# schematic.net
KiCad netlist of a schematic drawn in Altium Designer
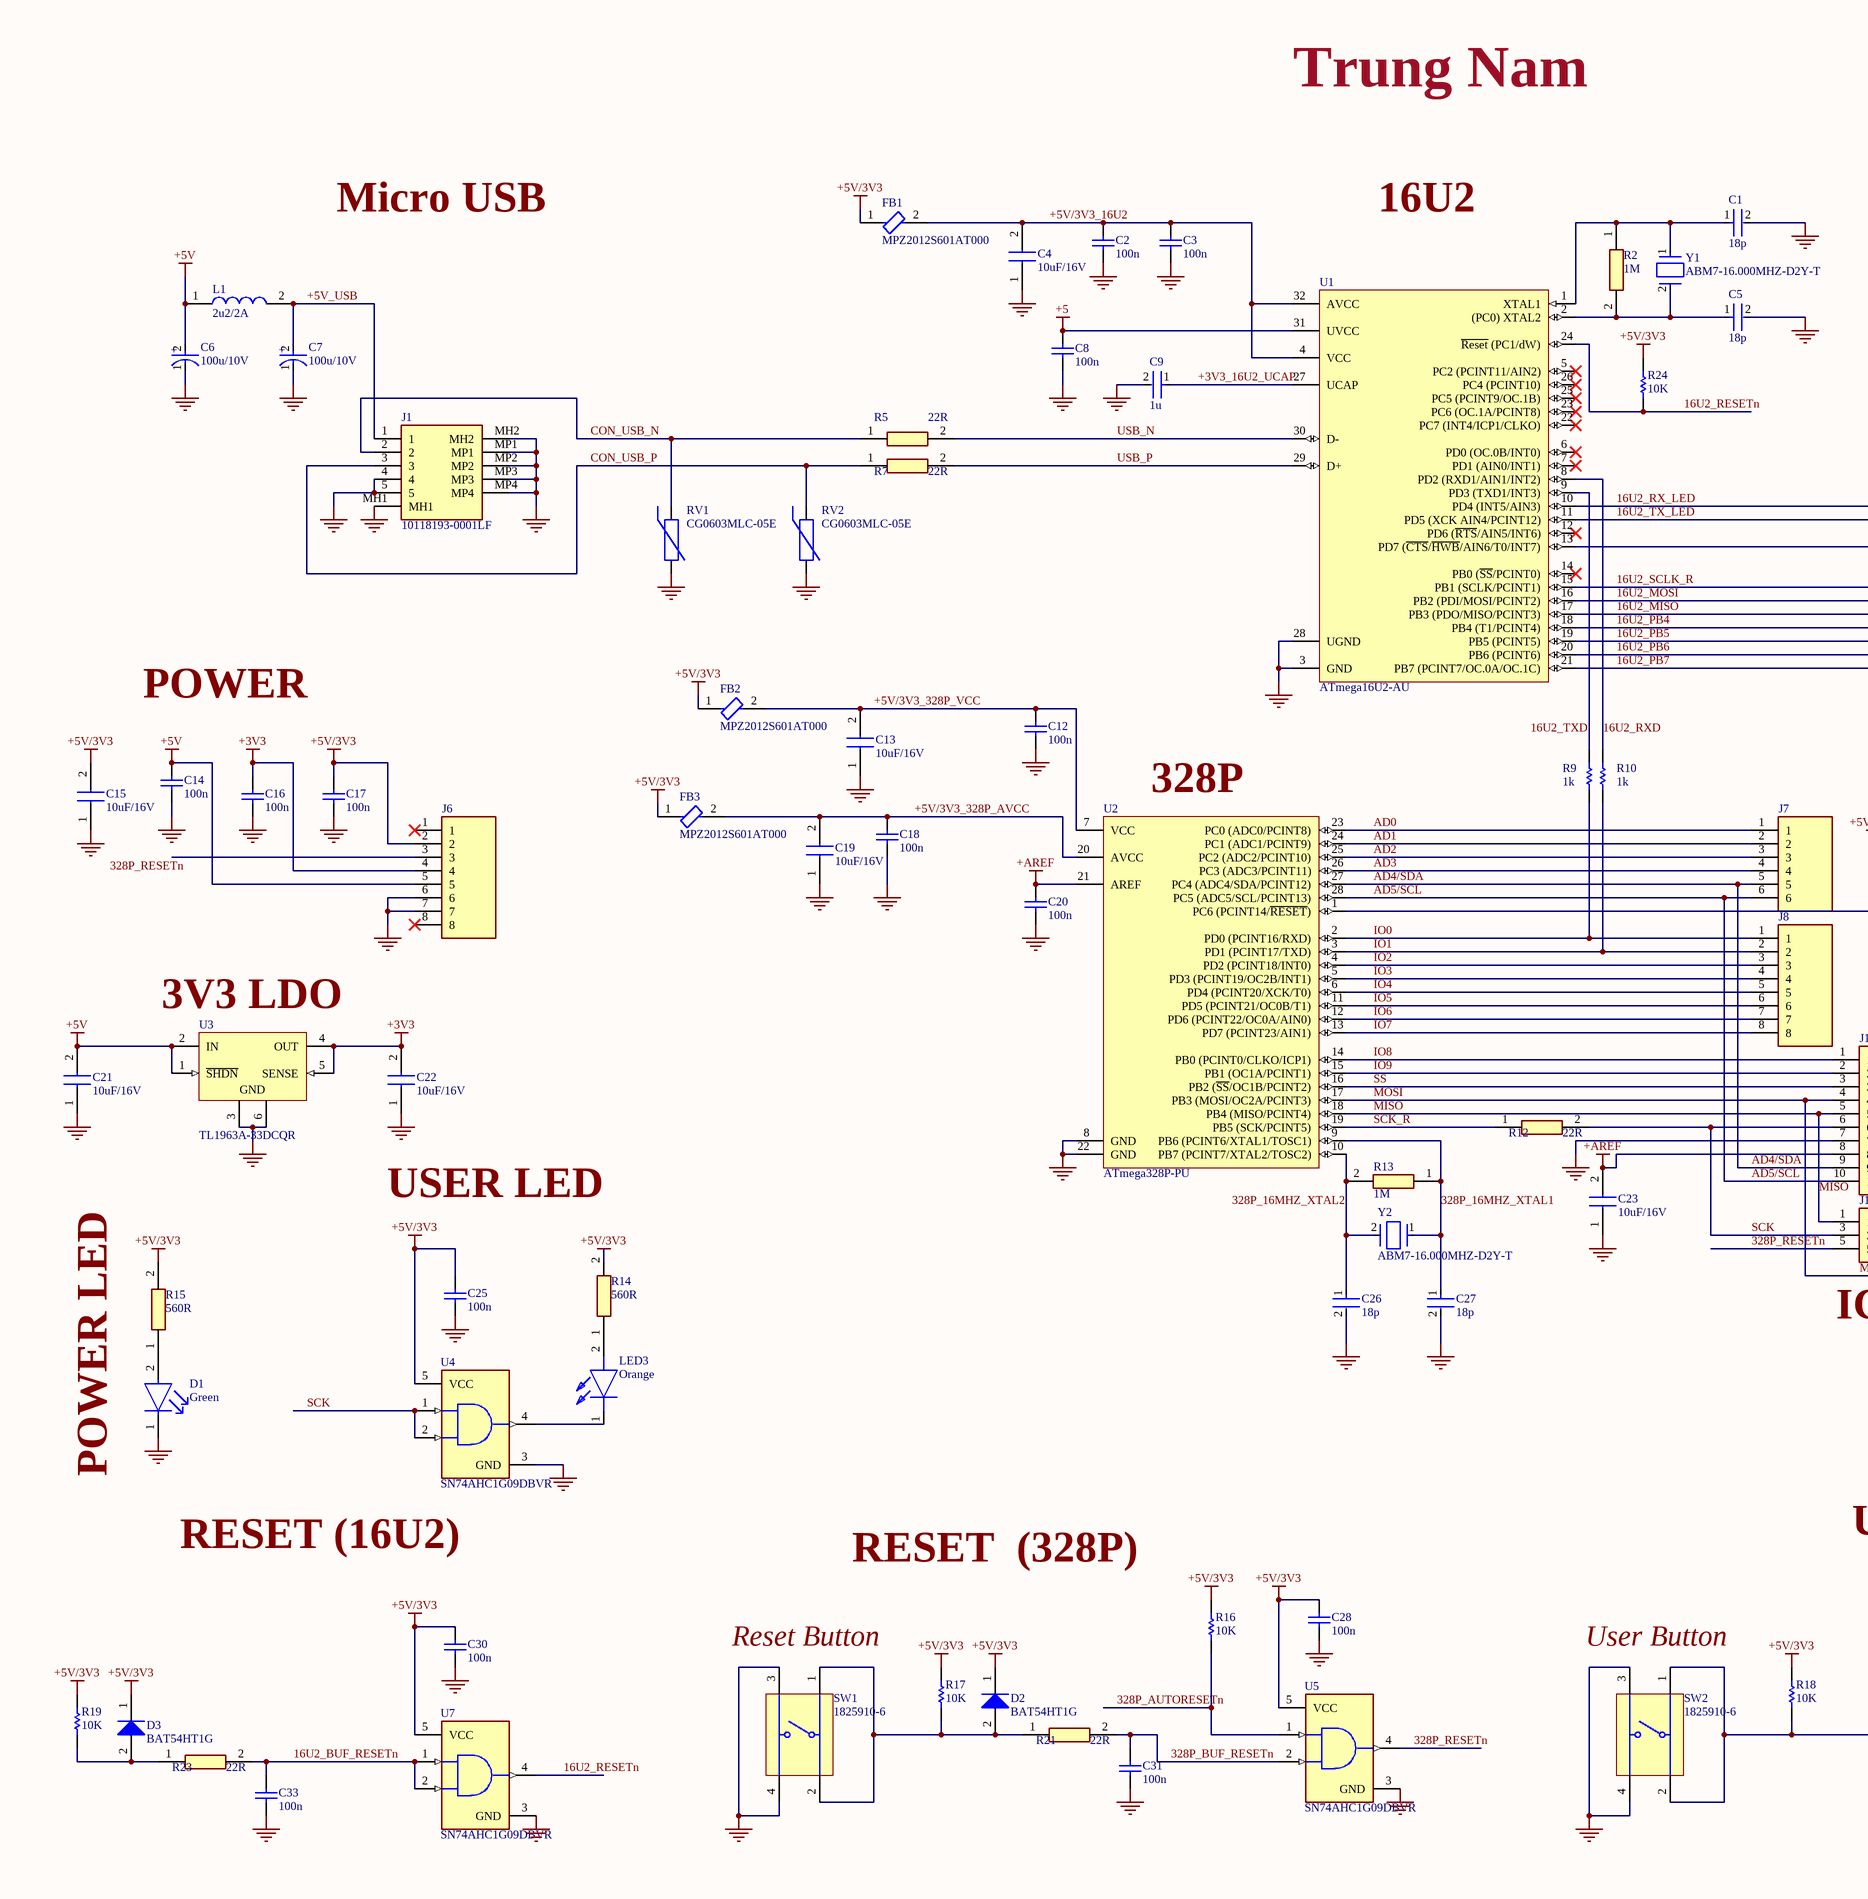
[diagram p0: schematic.SchDoc, left]
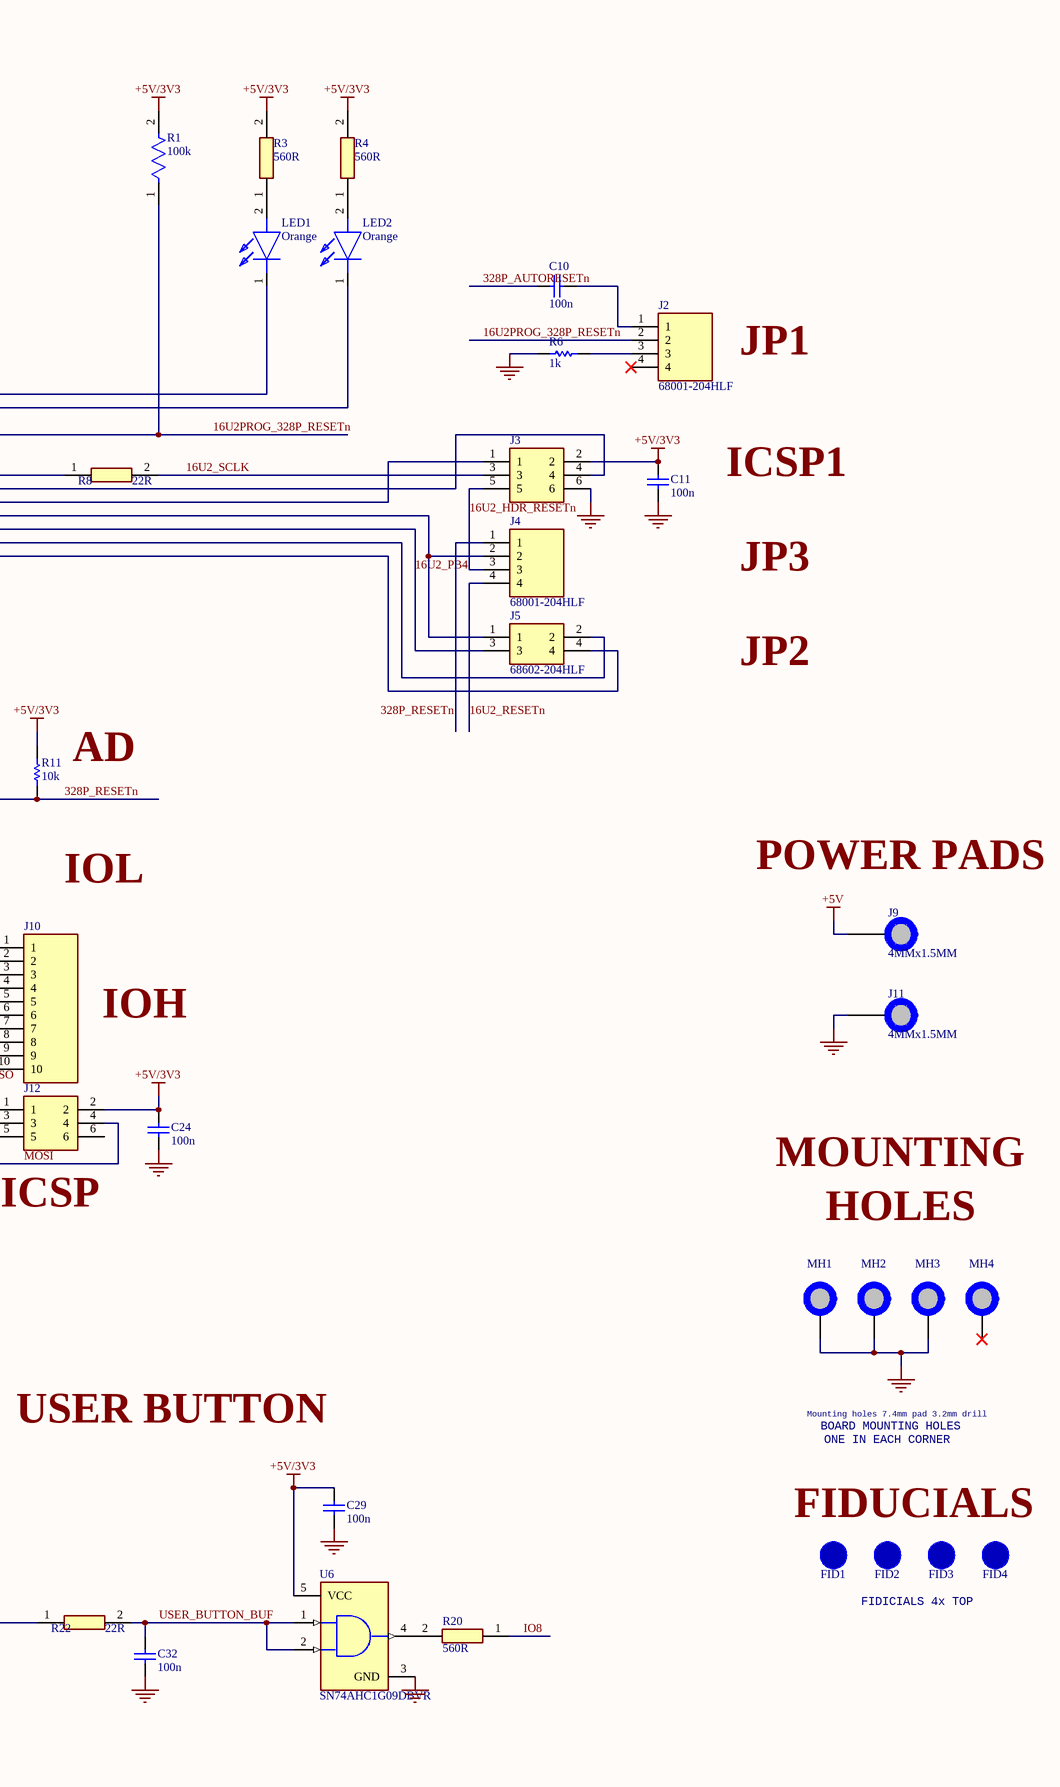
[diagram p1: schematic.SchDoc, right]

(export (version "E")
  (design (tool "Eeschema 10.0.6"))
  (components
    (comp (ref "C1")
      (value "18p")
      (footprint "FP-C0805C-DN-MFG")
      (description "CAP CER 18PF 50V C0G/NP0 0805")
      (fields
        (field (name "OCTOPART") "https://octopart.com/c0805c180j5gactu-kemet-144810")
        (field (name "TOLERANCE") "0.05")
      )
      (libsource (lib "Altium Content Vault") (part "b4654b650e69147ec39a6b967a45e02"))
    )
    (comp (ref "C2")
      (value "100n")
      (footprint "CAPC2013X145X20LL20")
      (description "Chip Capacitor, 0.1 uF, +/- 10%, 50 V, -55 to 125 degC, 0805 (2012 Metric), RoHS, Tape and Reel")
      (fields (field (name "MANUFACTURER") "TDK") (field (name "VOLTAGE") "50V"))
      (libsource (lib "Altium Content Vault") (part "CAP-NP-2"))
    )
    (comp (ref "C3")
      (value "100n")
      (footprint "CAPC2013X145X20LL20")
      (description "Chip Capacitor, 0.1 uF, +/- 10%, 50 V, -55 to 125 degC, 0805 (2012 Metric), RoHS, Tape and Reel")
      (fields (field (name "MANUFACTURER") "TDK") (field (name "VOLTAGE") "50V"))
      (libsource (lib "Altium Content Vault") (part "CAP-NP-2"))
    )
    (comp (ref "C4")
      (value "10uF/16V")
      (footprint "SamacSys:CAPC2012X145N")
      (description "Capacitor")
      (fields
        (field (name "MANUFACTURER_PART_NUMBER") "C2012X5R1C106M125AC")
        (field (name "MOUSER PART NUMBER") "810-C2012X5R1C106M-3")
      )
      (libsource (lib "SamacSys") (part "C2012X5R1C106M125AC"))
    )
    (comp (ref "C5")
      (value "18p")
      (footprint "FP-C0805C-DN-MFG")
      (description "CAP CER 18PF 50V C0G/NP0 0805")
      (fields
        (field (name "OCTOPART") "https://octopart.com/c0805c180j5gactu-kemet-144810")
        (field (name "TOLERANCE") "0.05")
      )
      (libsource (lib "Altium Content Vault") (part "b4654b650e69147ec39a6b967a45e02"))
    )
    (comp (ref "C6")
      (value "100u/10V")
      (footprint "FP-SC-MFG")
      (description "CAP ALUM 100UF 20% 10V SMD")
      (fields (field (name "TOLERANCE") "20%"))
      (libsource (lib "Altium Content Vault") (part "a00bbbee19879c290e62620ae7e47b1"))
    )
    (comp (ref "C7")
      (value "100u/10V")
      (footprint "FP-SC-MFG")
      (description "CAP ALUM 100UF 20% 10V SMD")
      (fields (field (name "TOLERANCE") "20%"))
      (libsource (lib "Altium Content Vault") (part "a00bbbee19879c290e62620ae7e47b1"))
    )
    (comp (ref "C8")
      (value "100n")
      (footprint "CAPC2013X145X20LL20")
      (description "Chip Capacitor, 0.1 uF, +/- 10%, 50 V, -55 to 125 degC, 0805 (2012 Metric), RoHS, Tape and Reel")
      (fields (field (name "MANUFACTURER") "TDK") (field (name "VOLTAGE") "50V"))
      (libsource (lib "Altium Content Vault") (part "CAP-NP-2"))
    )
    (comp (ref "C9")
      (value "1u")
      (footprint "FP-C2012-125-0_2-IPC_A")
      (description "Multilayer Ceramic Capacitors 1μF ±10% 25V X5R SMD 0805")
      (fields (field (name "VOLTAGE") "25V") (field (name "TOLERANCE") "10%"))
      (libsource (lib "Altium Content Vault") (part "b4654b650e69147ec39a6b967a45e02"))
    )
    (comp (ref "C10")
      (value "100n")
      (footprint "CAPC2013X145X20LL20")
      (description "Chip Capacitor, 0.1 uF, +/- 10%, 50 V, -55 to 125 degC, 0805 (2012 Metric), RoHS, Tape and Reel")
      (fields (field (name "MANUFACTURER") "TDK") (field (name "VOLTAGE") "50V"))
      (libsource (lib "Altium Content Vault") (part "CAP-NP-2"))
    )
    (comp (ref "C11")
      (value "100n")
      (footprint "CAPC2013X145X20LL20")
      (description "Chip Capacitor, 0.1 uF, +/- 10%, 50 V, -55 to 125 degC, 0805 (2012 Metric), RoHS, Tape and Reel")
      (fields (field (name "MANUFACTURER") "TDK") (field (name "VOLTAGE") "50V"))
      (libsource (lib "Altium Content Vault") (part "CAP-NP-2"))
    )
    (comp (ref "C12")
      (value "100n")
      (footprint "CAPC2013X145X20LL20")
      (description "Chip Capacitor, 0.1 uF, +/- 10%, 50 V, -55 to 125 degC, 0805 (2012 Metric), RoHS, Tape and Reel")
      (fields (field (name "MANUFACTURER") "TDK") (field (name "VOLTAGE") "50V"))
      (libsource (lib "Altium Content Vault") (part "CAP-NP-2"))
    )
    (comp (ref "C13")
      (value "10uF/16V")
      (footprint "SamacSys:CAPC2012X145N")
      (description "Capacitor")
      (fields
        (field (name "MANUFACTURER_PART_NUMBER") "C2012X5R1C106M125AC")
        (field (name "MOUSER PART NUMBER") "810-C2012X5R1C106M-3")
      )
      (libsource (lib "SamacSys") (part "C2012X5R1C106M125AC"))
    )
    (comp (ref "C14")
      (value "100n")
      (footprint "CAPC2013X145X20LL20")
      (description "Chip Capacitor, 0.1 uF, +/- 10%, 50 V, -55 to 125 degC, 0805 (2012 Metric), RoHS, Tape and Reel")
      (fields (field (name "MANUFACTURER") "TDK") (field (name "VOLTAGE") "50V"))
      (libsource (lib "Altium Content Vault") (part "CAP-NP-2"))
    )
    (comp (ref "C15")
      (value "10uF/16V")
      (footprint "SamacSys:CAPC2012X145N")
      (description "Capacitor")
      (fields
        (field (name "MANUFACTURER_PART_NUMBER") "C2012X5R1C106M125AC")
        (field (name "MOUSER PART NUMBER") "810-C2012X5R1C106M-3")
      )
      (libsource (lib "SamacSys") (part "C2012X5R1C106M125AC"))
    )
    (comp (ref "C16")
      (value "100n")
      (footprint "CAPC2013X145X20LL20")
      (description "Chip Capacitor, 0.1 uF, +/- 10%, 50 V, -55 to 125 degC, 0805 (2012 Metric), RoHS, Tape and Reel")
      (fields (field (name "MANUFACTURER") "TDK") (field (name "VOLTAGE") "50V"))
      (libsource (lib "Altium Content Vault") (part "CAP-NP-2"))
    )
    (comp (ref "C17")
      (value "100n")
      (footprint "CAPC2013X145X20LL20")
      (description "Chip Capacitor, 0.1 uF, +/- 10%, 50 V, -55 to 125 degC, 0805 (2012 Metric), RoHS, Tape and Reel")
      (fields (field (name "MANUFACTURER") "TDK") (field (name "VOLTAGE") "50V"))
      (libsource (lib "Altium Content Vault") (part "CAP-NP-2"))
    )
    (comp (ref "C18")
      (value "100n")
      (footprint "CAPC2013X145X20LL20")
      (description "Chip Capacitor, 0.1 uF, +/- 10%, 50 V, -55 to 125 degC, 0805 (2012 Metric), RoHS, Tape and Reel")
      (fields (field (name "MANUFACTURER") "TDK") (field (name "VOLTAGE") "50V"))
      (libsource (lib "Altium Content Vault") (part "CAP-NP-2"))
    )
    (comp (ref "C19")
      (value "10uF/16V")
      (footprint "SamacSys:CAPC2012X145N")
      (description "Capacitor")
      (fields
        (field (name "MANUFACTURER_PART_NUMBER") "C2012X5R1C106M125AC")
        (field (name "MOUSER PART NUMBER") "810-C2012X5R1C106M-3")
      )
      (libsource (lib "SamacSys") (part "C2012X5R1C106M125AC"))
    )
    (comp (ref "C20")
      (value "100n")
      (footprint "CAPC2013X145X20LL20")
      (description "Chip Capacitor, 0.1 uF, +/- 10%, 50 V, -55 to 125 degC, 0805 (2012 Metric), RoHS, Tape and Reel")
      (fields (field (name "MANUFACTURER") "TDK") (field (name "VOLTAGE") "50V"))
      (libsource (lib "Altium Content Vault") (part "CAP-NP-2"))
    )
    (comp (ref "C21")
      (value "10uF/16V")
      (footprint "SamacSys:CAPC2012X145N")
      (description "Capacitor")
      (fields
        (field (name "MANUFACTURER_PART_NUMBER") "C2012X5R1C106M125AC")
        (field (name "MOUSER PART NUMBER") "810-C2012X5R1C106M-3")
      )
      (libsource (lib "SamacSys") (part "C2012X5R1C106M125AC"))
    )
    (comp (ref "C22")
      (value "10uF/16V")
      (footprint "SamacSys:CAPC2012X145N")
      (description "Capacitor")
      (fields
        (field (name "MANUFACTURER_PART_NUMBER") "C2012X5R1C106M125AC")
        (field (name "MOUSER PART NUMBER") "810-C2012X5R1C106M-3")
      )
      (libsource (lib "SamacSys") (part "C2012X5R1C106M125AC"))
    )
    (comp (ref "C23")
      (value "10uF/16V")
      (footprint "SamacSys:CAPC2012X145N")
      (description "Capacitor")
      (fields
        (field (name "MANUFACTURER_PART_NUMBER") "C2012X5R1C106M125AC")
        (field (name "MOUSER PART NUMBER") "810-C2012X5R1C106M-3")
      )
      (libsource (lib "SamacSys") (part "C2012X5R1C106M125AC"))
    )
    (comp (ref "C24")
      (value "100n")
      (footprint "CAPC2013X145X20LL20")
      (description "Chip Capacitor, 0.1 uF, +/- 10%, 50 V, -55 to 125 degC, 0805 (2012 Metric), RoHS, Tape and Reel")
      (fields (field (name "MANUFACTURER") "TDK") (field (name "VOLTAGE") "50V"))
      (libsource (lib "Altium Content Vault") (part "CAP-NP-2"))
    )
    (comp (ref "C25")
      (value "100n")
      (footprint "CAPC2013X145X20LL20")
      (description "Chip Capacitor, 0.1 uF, +/- 10%, 50 V, -55 to 125 degC, 0805 (2012 Metric), RoHS, Tape and Reel")
      (fields (field (name "MANUFACTURER") "TDK") (field (name "VOLTAGE") "50V"))
      (libsource (lib "Altium Content Vault") (part "CAP-NP-2"))
    )
    (comp (ref "C26")
      (value "18p")
      (footprint "FP-C0805C-DN-MFG")
      (description "CAP CER 18PF 50V C0G/NP0 0805")
      (fields
        (field (name "OCTOPART") "https://octopart.com/c0805c180j5gactu-kemet-144810")
        (field (name "TOLERANCE") "0.05")
      )
      (libsource (lib "Altium Content Vault") (part "b4654b650e69147ec39a6b967a45e02"))
    )
    (comp (ref "C27")
      (value "18p")
      (footprint "FP-C0805C-DN-MFG")
      (description "CAP CER 18PF 50V C0G/NP0 0805")
      (fields
        (field (name "OCTOPART") "https://octopart.com/c0805c180j5gactu-kemet-144810")
        (field (name "TOLERANCE") "0.05")
      )
      (libsource (lib "Altium Content Vault") (part "b4654b650e69147ec39a6b967a45e02"))
    )
    (comp (ref "C28")
      (value "100n")
      (footprint "CAPC2013X145X20LL20")
      (description "Chip Capacitor, 0.1 uF, +/- 10%, 50 V, -55 to 125 degC, 0805 (2012 Metric), RoHS, Tape and Reel")
      (fields (field (name "MANUFACTURER") "TDK") (field (name "VOLTAGE") "50V"))
      (libsource (lib "Altium Content Vault") (part "CAP-NP-2"))
    )
    (comp (ref "C29")
      (value "100n")
      (footprint "CAPC2013X145X20LL20")
      (description "Chip Capacitor, 0.1 uF, +/- 10%, 50 V, -55 to 125 degC, 0805 (2012 Metric), RoHS, Tape and Reel")
      (fields (field (name "MANUFACTURER") "TDK") (field (name "VOLTAGE") "50V"))
      (libsource (lib "Altium Content Vault") (part "CAP-NP-2"))
    )
    (comp (ref "C30")
      (value "100n")
      (footprint "CAPC2013X145X20LL20")
      (description "Chip Capacitor, 0.1 uF, +/- 10%, 50 V, -55 to 125 degC, 0805 (2012 Metric), RoHS, Tape and Reel")
      (fields (field (name "MANUFACTURER") "TDK") (field (name "VOLTAGE") "50V"))
      (libsource (lib "Altium Content Vault") (part "CAP-NP-2"))
    )
    (comp (ref "C31")
      (value "100n")
      (footprint "CAPC2013X145X20LL20")
      (description "Chip Capacitor, 0.1 uF, +/- 10%, 50 V, -55 to 125 degC, 0805 (2012 Metric), RoHS, Tape and Reel")
      (fields (field (name "MANUFACTURER") "TDK") (field (name "VOLTAGE") "50V"))
      (libsource (lib "Altium Content Vault") (part "CAP-NP-2"))
    )
    (comp (ref "C32")
      (value "100n")
      (footprint "CAPC2013X145X20LL20")
      (description "Chip Capacitor, 0.1 uF, +/- 10%, 50 V, -55 to 125 degC, 0805 (2012 Metric), RoHS, Tape and Reel")
      (fields (field (name "MANUFACTURER") "TDK") (field (name "VOLTAGE") "50V"))
      (libsource (lib "Altium Content Vault") (part "CAP-NP-2"))
    )
    (comp (ref "C33")
      (value "100n")
      (footprint "CAPC2013X145X20LL20")
      (description "Chip Capacitor, 0.1 uF, +/- 10%, 50 V, -55 to 125 degC, 0805 (2012 Metric), RoHS, Tape and Reel")
      (fields (field (name "MANUFACTURER") "TDK") (field (name "VOLTAGE") "50V"))
      (libsource (lib "Altium Content Vault") (part "CAP-NP-2"))
    )
    (comp (ref "D1")
      (value "Green")
      (footprint "FP-LG_L29K-MFG")
      (description "LED GREEN DIFFUSED 0603 SMD")
      (libsource (lib "Altium Content Vault") (part "8706943c75ba83719d021d2fdc84c58"))
    )
    (comp (ref "D2")
      (value "BAT54HT1G")
      (footprint "ONSC-SOD-323-2-477-02_V")
      (description "Schottky Barrier Diode, 2-Pin SOD-323, Pb-Free, Tape and Reel")
      (fields (field (name "MANUFACTURER") "On Semiconductor"))
      (libsource (lib "Altium Content Vault") (part "ONSC-D-K1A2-2"))
    )
    (comp (ref "D3")
      (value "BAT54HT1G")
      (footprint "ONSC-SOD-323-2-477-02_V")
      (description "Schottky Barrier Diode, 2-Pin SOD-323, Pb-Free, Tape and Reel")
      (fields (field (name "MANUFACTURER") "On Semiconductor"))
      (libsource (lib "Altium Content Vault") (part "ONSC-D-K1A2-2"))
    )
    (comp (ref "FB1")
      (value "MPZ2012S601AT000")
      (footprint "FP-MPZ2012-MFG")
      (fields (field (name "TOLERANCE") "25%"))
      (libsource (lib "Altium Content Vault") (part "5f30dd21d616792df468990f7003faa"))
    )
    (comp (ref "FB2")
      (value "MPZ2012S601AT000")
      (footprint "FP-MPZ2012-MFG")
      (fields (field (name "TOLERANCE") "25%"))
      (libsource (lib "Altium Content Vault") (part "5f30dd21d616792df468990f7003faa"))
    )
    (comp (ref "FB3")
      (value "MPZ2012S601AT000")
      (footprint "FP-MPZ2012-MFG")
      (fields (field (name "TOLERANCE") "25%"))
      (libsource (lib "Altium Content Vault") (part "5f30dd21d616792df468990f7003faa"))
    )
    (comp (ref "FID1")
      (value "FID_1MMC")
      (footprint "FID_40X120D")
      (description "Fiducial 40mil Diameter, 120mil Mask")
      (libsource (lib "Integrated_Library_FEDEVEL_APR_2015") (part "FID_1MMC"))
    )
    (comp (ref "FID2")
      (value "FID_1MMC")
      (footprint "FID_40X120D")
      (description "Fiducial 40mil Diameter, 120mil Mask")
      (libsource (lib "Integrated_Library_FEDEVEL_APR_2015") (part "FID_1MMC"))
    )
    (comp (ref "FID3")
      (value "FID_1MMC")
      (footprint "FID_40X120D")
      (description "Fiducial 40mil Diameter, 120mil Mask")
      (libsource (lib "Integrated_Library_FEDEVEL_APR_2015") (part "FID_1MMC"))
    )
    (comp (ref "FID4")
      (value "FID_1MMC")
      (footprint "FID_40X120D")
      (description "Fiducial 40mil Diameter, 120mil Mask")
      (libsource (lib "Integrated_Library_FEDEVEL_APR_2015") (part "FID_1MMC"))
    )
    (comp (ref "J1")
      (value "10118193-0001LF")
      (footprint "SamacSys:101181930001LF")
      (description "Connector")
      (libsource (lib "*") (part "10118193-0001LF"))
    )
    (comp (ref "J2")
      (value "68001-204HLF")
      (footprint "SamacSys:HDRV4W67P0X254_1X4_1016X241X858P")
      (description "Connector")
      (libsource (lib "SamacSys") (part "68001-204HLF"))
    )
    (comp (ref "J3")
      (value "A2541WV-2x3P-C808D808-G15")
      (footprint "SamacSys:HDRV6W64P254_2X3_762X508X533P")
      (description "Connector")
      (libsource (lib "SamacSys") (part "A2541WV-2x3P-C808D808-G15"))
    )
    (comp (ref "J4")
      (value "68001-204HLF")
      (footprint "SamacSys:HDRV4W67P0X254_1X4_1016X241X858P")
      (description "Connector")
      (libsource (lib "SamacSys") (part "68001-204HLF"))
    )
    (comp (ref "J5")
      (value "68602-204HLF")
      (footprint "SamacSys:HDRV4W67P254_2X2_508X483X888P")
      (description "Connector")
      (fields (field (name "MOUSER PART NUMBER") "649-68602-204HLF"))
      (libsource (lib "SamacSys") (part "68602-204HLF"))
    )
    (comp (ref "J6")
      (value "M20-7820842")
      (footprint "SamacSys:RHDR8W80P0X254_1X8_2032X254X850P")
      (description "Connector")
      (fields (field (name "MOUSER PART NUMBER") "855-M20-7820842"))
      (libsource (lib "SamacSys") (part "M20-7820842"))
    )
    (comp (ref "J7")
      (value "M20-7820646")
      (footprint "SamacSys:HDRV6W70P0X254_1X6_1564X250X865P")
      (description "Connector")
      (fields (field (name "MOUSER PART NUMBER") "855-M20-7820646"))
      (libsource (lib "SamacSys") (part "M20-7820646"))
    )
    (comp (ref "J8")
      (value "M20-7820842")
      (footprint "SamacSys:RHDR8W80P0X254_1X8_2032X254X850P")
      (description "Connector")
      (fields (field (name "MOUSER PART NUMBER") "855-M20-7820842"))
      (libsource (lib "SamacSys") (part "M20-7820842"))
    )
    (comp (ref "J9")
      (value "4MMx1.5MM")
      (footprint "PAD_WITH_HOLE_4MMx1.5MM")
      (description "Pad with a hole 4mm x 1.5mm")
      (libsource (lib "Integrated_Library_FEDEVEL_APR_2015") (part "PAD_WITH_HOLE_4MMx1.5MM"))
    )
    (comp (ref "J10")
      (value "M20-7821046")
      (footprint "SamacSys:RHDR10W70P0X254_1X10_2580X250X865P")
      (description "Connector")
      (fields (field (name "MOUSER PART NUMBER") "855-M20-7821046"))
      (libsource (lib "SamacSys") (part "M20-7821046"))
    )
    (comp (ref "J11")
      (value "4MMx1.5MM")
      (footprint "PAD_WITH_HOLE_4MMx1.5MM")
      (description "Pad with a hole 4mm x 1.5mm")
      (libsource (lib "Integrated_Library_FEDEVEL_APR_2015") (part "PAD_WITH_HOLE_4MMx1.5MM"))
    )
    (comp (ref "J12")
      (value "A2541WV-2x3P-C808D808-G15")
      (footprint "SamacSys:HDRV6W64P254_2X3_762X508X533P")
      (description "Connector")
      (libsource (lib "SamacSys") (part "A2541WV-2x3P-C808D808-G15"))
    )
    (comp (ref "L1")
      (value "2u2/2A")
      (footprint "SamacSys:INDC3225X270N")
      (description "Inductor")
      (fields
        (field (name "MANUFACTURER_PART_NUMBER") "L1210R2R2MDWIT")
        (field (name "MOUSER PART NUMBER") "80-L1210R2R2MDWIT")
      )
      (libsource (lib "*") (part "L1210R2R2MDWIT"))
    )
    (comp (ref "LED1")
      (value "Orange")
      (footprint "SamacSys:SODFL1708X67N")
      (description "LED")
      (fields
        (field (name "MANUFACTURER_PART_NUMBER") "LO L29K-H2K1-24-Z")
        (field (name "MOUSER PART NUMBER") "720-LOL29KH2K124Z")
      )
      (libsource (lib "*") (part "LO_L29K-H2K1-24-Z"))
    )
    (comp (ref "LED2")
      (value "Orange")
      (footprint "SamacSys:SODFL1708X67N")
      (description "LED")
      (fields
        (field (name "MANUFACTURER_PART_NUMBER") "LO L29K-H2K1-24-Z")
        (field (name "MOUSER PART NUMBER") "720-LOL29KH2K124Z")
      )
      (libsource (lib "*") (part "LO_L29K-H2K1-24-Z"))
    )
    (comp (ref "LED3")
      (value "Orange")
      (footprint "SamacSys:SODFL1708X67N")
      (description "LED")
      (fields
        (field (name "MANUFACTURER_PART_NUMBER") "LO L29K-H2K1-24-Z")
        (field (name "MOUSER PART NUMBER") "720-LOL29KH2K124Z")
      )
      (libsource (lib "*") (part "LO_L29K-H2K1-24-Z"))
    )
    (comp (ref "MH1")
      (value "MH_7.4MMC_3.2MMD")
      (footprint "MH_7.4MMD_3.2MMD")
      (description "Mounting Hole 7.4mm Diameter, 3.2mm Drill")
      (fields (field (name ".CREATOR") "MM"))
      (libsource (lib "Integrated_Library_FEDEVEL_APR_2015") (part "MH_7.4MMC_3.2MMD"))
    )
    (comp (ref "MH2")
      (value "MH_7.4MMC_3.2MMD")
      (footprint "MH_7.4MMD_3.2MMD")
      (description "Mounting Hole 7.4mm Diameter, 3.2mm Drill")
      (fields (field (name ".CREATOR") "MM"))
      (libsource (lib "Integrated_Library_FEDEVEL_APR_2015") (part "MH_7.4MMC_3.2MMD"))
    )
    (comp (ref "MH3")
      (value "MH_7.4MMC_3.2MMD")
      (footprint "MH_7.4MMD_3.2MMD")
      (description "Mounting Hole 7.4mm Diameter, 3.2mm Drill")
      (fields (field (name ".CREATOR") "MM"))
      (libsource (lib "Integrated_Library_FEDEVEL_APR_2015") (part "MH_7.4MMC_3.2MMD"))
    )
    (comp (ref "MH4")
      (value "MH_7.4MMNC_3.2MMD")
      (footprint "MH_7.4MMD_3.2MMD_NON_COPPER_NPTH")
      (description "Mounting Hole 7.4mm Diameter (Non Copper), 3.2mm Drill NPTH")
      (libsource (lib "Integrated_Library_FEDEVEL_APR_2015") (part "MH_7.4MMNC_3.2MMD"))
    )
    (comp (ref "R1")
      (value "100k")
      (footprint "FP-RC0805-0_6-IPC_C")
      (description "RES 100K OHM 1% 1/8W 0805")
      (fields (field (name "TOLERANCE") "1%"))
      (libsource (lib "Altium Content Vault") (part "1029c3af85768c4190bb7ad29bc67b5"))
    )
    (comp (ref "R2")
      (value "1M")
      (footprint "SamacSys:RESC2012X60N")
      (description "Resistor")
      (fields
        (field (name "MANUFACTURER_PART_NUMBER") "RC0805FR-071ML")
        (field (name "MOUSER PART NUMBER") "603-RC0805FR-071ML")
      )
      (libsource (lib "") (part "RC0805FR-071ML_1"))
    )
    (comp (ref "R3")
      (value "560R")
      (footprint "SamacSys:RESC2012X60N")
      (description "Resistor")
      (fields
        (field (name "MANUFACTURER_PART_NUMBER") "RC0805FR-07560RL")
        (field (name "MOUSER PART NUMBER") "603-RC0805FR-07560RL")
      )
      (libsource (lib "*") (part "RC0805FR-07560RL"))
    )
    (comp (ref "R4")
      (value "560R")
      (footprint "SamacSys:RESC2012X60N")
      (description "Resistor")
      (fields
        (field (name "MANUFACTURER_PART_NUMBER") "RC0805FR-07560RL")
        (field (name "MOUSER PART NUMBER") "603-RC0805FR-07560RL")
      )
      (libsource (lib "*") (part "RC0805FR-07560RL"))
    )
    (comp (ref "R5")
      (value "22R")
      (footprint "SamacSys:RESC2012X60N")
      (description "Resistor")
      (fields
        (field (name "MANUFACTURER_PART_NUMBER") "RC0805FR-0722RL")
        (field (name "MOUSER PART NUMBER") "603-RC0805FR-0722RL")
      )
      (libsource (lib "*") (part "RC0805FR-0722RL"))
    )
    (comp (ref "R6")
      (value "1k")
      (footprint "RESC2013X60X35ML10T20")
      (description "Chip Resistor, 1 KOhm, +/- 1%, 125 mW, -55 to 155 degC, 0805 (2012 Metric), RoHS, Tape and Reel")
      (fields (field (name "TOLERANCE") "1%") (field (name "MANUFACTURER") "Yageo"))
      (libsource (lib "Altium Content Vault") (part "RES-2"))
    )
    (comp (ref "R7")
      (value "22R")
      (footprint "SamacSys:RESC2012X60N")
      (description "Resistor")
      (fields
        (field (name "MANUFACTURER_PART_NUMBER") "RC0805FR-0722RL")
        (field (name "MOUSER PART NUMBER") "603-RC0805FR-0722RL")
      )
      (libsource (lib "*") (part "RC0805FR-0722RL"))
    )
    (comp (ref "R8")
      (value "22R")
      (footprint "SamacSys:RESC2012X60N")
      (description "Resistor")
      (fields
        (field (name "MANUFACTURER_PART_NUMBER") "RC0805FR-0722RL")
        (field (name "MOUSER PART NUMBER") "603-RC0805FR-0722RL")
      )
      (libsource (lib "*") (part "RC0805FR-0722RL"))
    )
    (comp (ref "R9")
      (value "1k")
      (footprint "RESC2013X60X35ML10T20")
      (description "Chip Resistor, 1 KOhm, +/- 1%, 125 mW, -55 to 155 degC, 0805 (2012 Metric), RoHS, Tape and Reel")
      (fields (field (name "TOLERANCE") "1%") (field (name "MANUFACTURER") "Yageo"))
      (libsource (lib "Altium Content Vault") (part "RES-2"))
    )
    (comp (ref "R10")
      (value "1k")
      (footprint "RESC2013X60X35ML10T20")
      (description "Chip Resistor, 1 KOhm, +/- 1%, 125 mW, -55 to 155 degC, 0805 (2012 Metric), RoHS, Tape and Reel")
      (fields (field (name "TOLERANCE") "1%") (field (name "MANUFACTURER") "Yageo"))
      (libsource (lib "Altium Content Vault") (part "RES-2"))
    )
    (comp (ref "R11")
      (value "10k")
      (footprint "RESC2013X60X35NL10T20")
      (description "Chip Resistor, 10 KOhm, +/- 1%, 0.125 W, -55 to 155 degC, 0805 (2012 Metric), RoHS, Tape and Reel")
      (fields (field (name "MANUFACTURER") "Yageo"))
      (libsource (lib "Altium Content Vault") (part "RES-2"))
    )
    (comp (ref "R12")
      (value "22R")
      (footprint "SamacSys:RESC2012X60N")
      (description "Resistor")
      (fields
        (field (name "MANUFACTURER_PART_NUMBER") "RC0805FR-0722RL")
        (field (name "MOUSER PART NUMBER") "603-RC0805FR-0722RL")
      )
      (libsource (lib "*") (part "RC0805FR-0722RL"))
    )
    (comp (ref "R13")
      (value "1M")
      (footprint "SamacSys:RESC2012X60N")
      (description "Resistor")
      (fields
        (field (name "MANUFACTURER_PART_NUMBER") "RC0805FR-071ML")
        (field (name "MOUSER PART NUMBER") "603-RC0805FR-071ML")
      )
      (libsource (lib "*") (part "RC0805FR-071ML"))
    )
    (comp (ref "R14")
      (value "560R")
      (footprint "SamacSys:RESC2012X60N")
      (description "Resistor")
      (fields
        (field (name "MANUFACTURER_PART_NUMBER") "RC0805FR-07560RL")
        (field (name "MOUSER PART NUMBER") "603-RC0805FR-07560RL")
      )
      (libsource (lib "*") (part "RC0805FR-07560RL"))
    )
    (comp (ref "R15")
      (value "560R")
      (footprint "SamacSys:RESC2012X60N")
      (description "Resistor")
      (fields
        (field (name "MANUFACTURER_PART_NUMBER") "RC0805FR-07560RL")
        (field (name "MOUSER PART NUMBER") "603-RC0805FR-07560RL")
      )
      (libsource (lib "*") (part "RC0805FR-07560RL"))
    )
    (comp (ref "R16")
      (value "10K")
      (footprint "RESC2013X60X35NL10T20")
      (description "Chip Resistor, 10 KOhm, +/- 1%, 0.125 W, -55 to 155 degC, 0805 (2012 Metric), RoHS, Tape and Reel")
      (fields (field (name "MANUFACTURER") "Yageo"))
      (libsource (lib "Altium Content Vault") (part "RES-2"))
    )
    (comp (ref "R17")
      (value "10K")
      (footprint "RESC2013X60X35NL10T20")
      (description "Chip Resistor, 10 KOhm, +/- 1%, 0.125 W, -55 to 155 degC, 0805 (2012 Metric), RoHS, Tape and Reel")
      (fields (field (name "MANUFACTURER") "Yageo"))
      (libsource (lib "Altium Content Vault") (part "RES-2"))
    )
    (comp (ref "R18")
      (value "10K")
      (footprint "RESC2013X60X35NL10T20")
      (description "Chip Resistor, 10 KOhm, +/- 1%, 0.125 W, -55 to 155 degC, 0805 (2012 Metric), RoHS, Tape and Reel")
      (fields (field (name "MANUFACTURER") "Yageo"))
      (libsource (lib "Altium Content Vault") (part "RES-2"))
    )
    (comp (ref "R19")
      (value "10K")
      (footprint "RESC2013X60X35NL10T20")
      (description "Chip Resistor, 10 KOhm, +/- 1%, 0.125 W, -55 to 155 degC, 0805 (2012 Metric), RoHS, Tape and Reel")
      (fields (field (name "MANUFACTURER") "Yageo"))
      (libsource (lib "Altium Content Vault") (part "RES-2"))
    )
    (comp (ref "R20")
      (value "560R")
      (footprint "SamacSys:RESC2012X60N")
      (description "Resistor")
      (fields
        (field (name "MANUFACTURER_PART_NUMBER") "RC0805FR-07560RL")
        (field (name "MOUSER PART NUMBER") "603-RC0805FR-07560RL")
      )
      (libsource (lib "") (part "RC0805FR-07560RL_1"))
    )
    (comp (ref "R21")
      (value "22R")
      (footprint "SamacSys:RESC2012X60N")
      (description "Resistor")
      (fields
        (field (name "MANUFACTURER_PART_NUMBER") "RC0805FR-0722RL")
        (field (name "MOUSER PART NUMBER") "603-RC0805FR-0722RL")
      )
      (libsource (lib "*") (part "RC0805FR-0722RL"))
    )
    (comp (ref "R22")
      (value "22R")
      (footprint "SamacSys:RESC2012X60N")
      (description "Resistor")
      (fields
        (field (name "MANUFACTURER_PART_NUMBER") "RC0805FR-0722RL")
        (field (name "MOUSER PART NUMBER") "603-RC0805FR-0722RL")
      )
      (libsource (lib "*") (part "RC0805FR-0722RL"))
    )
    (comp (ref "R23")
      (value "22R")
      (footprint "SamacSys:RESC2012X60N")
      (description "Resistor")
      (fields
        (field (name "MANUFACTURER_PART_NUMBER") "RC0805FR-0722RL")
        (field (name "MOUSER PART NUMBER") "603-RC0805FR-0722RL")
      )
      (libsource (lib "*") (part "RC0805FR-0722RL"))
    )
    (comp (ref "R24")
      (value "10K")
      (footprint "RESC2013X60X35NL10T20")
      (description "Chip Resistor, 10 KOhm, +/- 1%, 0.125 W, -55 to 155 degC, 0805 (2012 Metric), RoHS, Tape and Reel")
      (fields (field (name "MANUFACTURER") "Yageo"))
      (libsource (lib "Altium Content Vault") (part "RES-2"))
    )
    (comp (ref "RV1")
      (value "CG0603MLC-05E")
      (footprint "BOUR-CG0603-2_V")
      (description "ESD Protector, 5 V Supply, -40 to 85 degC, 1.6 x 0.8 x 0.55 mm SMD, RoHS, Tape and Reel")
      (fields (field (name "MANUFACTURER") "Bourns"))
      (libsource (lib "Altium Content Vault") (part "BOUR-VSR-2"))
    )
    (comp (ref "RV2")
      (value "CG0603MLC-05E")
      (footprint "BOUR-CG0603-2_V")
      (description "ESD Protector, 5 V Supply, -40 to 85 degC, 1.6 x 0.8 x 0.55 mm SMD, RoHS, Tape and Reel")
      (fields (field (name "MANUFACTURER") "Bourns"))
      (libsource (lib "Altium Content Vault") (part "BOUR-VSR-2"))
    )
    (comp (ref "SW1")
      (value "1825910-6")
      (footprint "TECO-1825910-6_V")
      (description "Tact Switch, SPST-NO, 0.05 A, -35 to 85 degC, 4-Pin THD, RoHS, Bulk")
      (fields (field (name "MANUFACTURER") "TE Connectivity"))
      (libsource (lib "Altium Content Vault") (part "SW-SPST-4_A"))
    )
    (comp (ref "SW2")
      (value "1825910-6")
      (footprint "TECO-1825910-6_V")
      (description "Tact Switch, SPST-NO, 0.05 A, -35 to 85 degC, 4-Pin THD, RoHS, Bulk")
      (fields (field (name "MANUFACTURER") "TE Connectivity"))
      (libsource (lib "Altium Content Vault") (part "SW-SPST-4_A"))
    )
    (comp (ref "U1")
      (value "ATmega16U2-AU")
      (footprint "32A_M")
      (libsource (lib "Altium Content Vault") (part "MC-8B-ATM8U2-SQ32"))
    )
    (comp (ref "U2")
      (value "ATmega328P-PU")
      (footprint "28P3")
      (libsource (lib "Altium Content Vault") (part "MC-8B-ATM48-IL28"))
    )
    (comp (ref "U3")
      (value "TL1963A-33DCQR")
      (footprint "DCQ0006A_L")
      (fields (field (name "MANUFACTURER") "Texas Instruments"))
      (libsource (lib "Altium Content Vault") (part "TI-TXXXXAXXXDCQ_KTTX"))
    )
    (comp (ref "U4")
      (value "SN74AHC1G09DBVR")
      (footprint "FP-DBV0005A-MFG")
      (description "IC GATE AND 1CH 2-INP SOT23-5")
      (fields
        (field (name "MANUFACTURER") "Texas Instruments")
        (field (name "OCTOPART") "https://octopart.com/sn74ahc1g09dbvr-texas+instruments-20351419")
      )
      (libsource (lib "Altium Content Vault") (part "77ee978384767e9857e3f2f804c3e10"))
    )
    (comp (ref "U5")
      (value "SN74AHC1G09DBVR")
      (footprint "FP-DBV0005A-MFG")
      (description "IC GATE AND 1CH 2-INP SOT23-5")
      (fields
        (field (name "MANUFACTURER") "Texas Instruments")
        (field (name "OCTOPART") "https://octopart.com/sn74ahc1g09dbvr-texas+instruments-20351419")
      )
      (libsource (lib "Altium Content Vault") (part "77ee978384767e9857e3f2f804c3e10"))
    )
    (comp (ref "U6")
      (value "SN74AHC1G09DBVR")
      (footprint "FP-DBV0005A-MFG")
      (description "IC GATE AND 1CH 2-INP SOT23-5")
      (fields
        (field (name "MANUFACTURER") "Texas Instruments")
        (field (name "OCTOPART") "https://octopart.com/sn74ahc1g09dbvr-texas+instruments-20351419")
      )
      (libsource (lib "Altium Content Vault") (part "77ee978384767e9857e3f2f804c3e10"))
    )
    (comp (ref "U7")
      (value "SN74AHC1G09DBVR")
      (footprint "FP-DBV0005A-MFG")
      (description "IC GATE AND 1CH 2-INP SOT23-5")
      (fields
        (field (name "MANUFACTURER") "Texas Instruments")
        (field (name "OCTOPART") "https://octopart.com/sn74ahc1g09dbvr-texas+instruments-20351419")
      )
      (libsource (lib "Altium Content Vault") (part "77ee978384767e9857e3f2f804c3e10"))
    )
    (comp (ref "Y1")
      (value "ABM7-16.000MHZ-D2Y-T")
      (footprint "FP-ABM7-MFG")
      (description "Crystal 16MHz ±20ppm 18pF SMD-2 6mm x 3.5mm")
      (fields (field (name "TOLERANCE") "20ppm"))
      (libsource (lib "Altium Content Vault") (part "c23a69dc6c9e2f18f2079038eb95dd1"))
    )
    (comp (ref "Y2")
      (value "ABM7-16.000MHZ-D2Y-T")
      (footprint "FP-ABM7-MFG")
      (description "Crystal 16MHz ±20ppm 18pF SMD-2 6mm x 3.5mm")
      (fields (field (name "TOLERANCE") "20ppm"))
      (libsource (lib "Altium Content Vault") (part "c23a69dc6c9e2f18f2079038eb95dd1"))
    )
  )
  (nets
    (net (code "1") (name "+3V3") (class "Default")
      (node (ref "C16") (pin "2") (pinfunction "2_2") (pintype "passive"))
      (node (ref "C22") (pin "2") (pinfunction "2_2") (pintype "passive"))
      (node (ref "J6") (pin "4") (pinfunction "4_4") (pintype "passive"))
      (node (ref "U3") (pin "4") (pinfunction "OUT_4") (pintype "power_in"))
      (node (ref "U3") (pin "5") (pinfunction "SENSE_5") (pintype "input"))
    )
    (net (code "2") (name "+5") (class "Default")
      (node (ref "C8") (pin "2") (pinfunction "2_2") (pintype "passive"))
      (node (ref "U1") (pin "31") (pinfunction "UVCC_31") (pintype "power_in"))
    )
    (net (code "3") (name "+5V") (class "Default")
      (node (ref "C14") (pin "2") (pinfunction "2_2") (pintype "passive"))
      (node (ref "C21") (pin "2") (pinfunction "2_2") (pintype "passive"))
      (node (ref "C6") (pin "2") (pinfunction "A_2") (pintype "passive"))
      (node (ref "J6") (pin "5") (pinfunction "5_5") (pintype "passive"))
      (node (ref "J9") (pin "1") (pinfunction "1_1") (pintype "passive"))
      (node (ref "L1") (pin "1") (pinfunction "1_1") (pintype "passive"))
      (node (ref "U3") (pin "1") (pinfunction "~{SHDN}_1") (pintype "input"))
      (node (ref "U3") (pin "2") (pinfunction "IN_2") (pintype "power_in"))
    )
    (net (code "4") (name "+5V{slash}3V3") (class "Default")
      (node (ref "C11") (pin "2") (pinfunction "2_2") (pintype "passive"))
      (node (ref "C15") (pin "2") (pinfunction "2_2") (pintype "passive"))
      (node (ref "C17") (pin "2") (pinfunction "2_2") (pintype "passive"))
      (node (ref "C24") (pin "2") (pinfunction "2_2") (pintype "passive"))
      (node (ref "C25") (pin "2") (pinfunction "2_2") (pintype "passive"))
      (node (ref "C28") (pin "2") (pinfunction "2_2") (pintype "passive"))
      (node (ref "C29") (pin "2") (pinfunction "2_2") (pintype "passive"))
      (node (ref "C30") (pin "2") (pinfunction "2_2") (pintype "passive"))
      (node (ref "D2") (pin "1") (pinfunction "K_1") (pintype "passive"))
      (node (ref "D3") (pin "1") (pinfunction "K_1") (pintype "passive"))
      (node (ref "FB1") (pin "1") (pinfunction "1_1") (pintype "passive"))
      (node (ref "FB2") (pin "1") (pinfunction "1_1") (pintype "passive"))
      (node (ref "FB3") (pin "1") (pinfunction "1_1") (pintype "passive"))
      (node (ref "J12") (pin "2") (pinfunction "2_2") (pintype "passive"))
      (node (ref "J3") (pin "2") (pinfunction "2_2") (pintype "passive"))
      (node (ref "J6") (pin "2") (pinfunction "2_2") (pintype "passive"))
      (node (ref "R1") (pin "2") (pinfunction "2_2") (pintype "passive"))
      (node (ref "R11") (pin "2") (pinfunction "2_2") (pintype "passive"))
      (node (ref "R14") (pin "2") (pinfunction "2_2") (pintype "passive"))
      (node (ref "R15") (pin "2") (pinfunction "2_2") (pintype "passive"))
      (node (ref "R16") (pin "2") (pinfunction "2_2") (pintype "passive"))
      (node (ref "R17") (pin "2") (pinfunction "2_2") (pintype "passive"))
      (node (ref "R18") (pin "2") (pinfunction "2_2") (pintype "passive"))
      (node (ref "R19") (pin "2") (pinfunction "2_2") (pintype "passive"))
      (node (ref "R24") (pin "2") (pinfunction "2_2") (pintype "passive"))
      (node (ref "R3") (pin "2") (pinfunction "2_2") (pintype "passive"))
      (node (ref "R4") (pin "2") (pinfunction "2_2") (pintype "passive"))
      (node (ref "U4") (pin "5") (pinfunction "VCC_5") (pintype "power_in"))
      (node (ref "U5") (pin "5") (pinfunction "VCC_5") (pintype "power_in"))
      (node (ref "U6") (pin "5") (pinfunction "VCC_5") (pintype "power_in"))
      (node (ref "U7") (pin "5") (pinfunction "VCC_5") (pintype "power_in"))
    )
    (net (code "5") (name "+AREF") (class "Default")
      (node (ref "C20") (pin "2") (pinfunction "2_2") (pintype "passive"))
      (node (ref "C23") (pin "2") (pinfunction "2_2") (pintype "passive"))
      (node (ref "J10") (pin "8") (pinfunction "8_8") (pintype "passive"))
      (node (ref "U2") (pin "21") (pinfunction "AREF_21") (pintype "power_in"))
    )
    (net (code "6") (name "/+3V3_16U2_UCAP") (class "Default")
      (node (ref "C9") (pin "1") (pinfunction "1_1") (pintype "passive"))
      (node (ref "U1") (pin "27") (pinfunction "UCAP_27") (pintype "power_in"))
    )
    (net (code "7") (name "/+5V_USB") (class "Default")
      (node (ref "C7") (pin "2") (pinfunction "A_2") (pintype "passive"))
      (node (ref "J1") (pin "1") (pinfunction "1_1") (pintype "passive"))
      (node (ref "L1") (pin "2") (pinfunction "2_2") (pintype "passive"))
    )
    (net (code "8") (name "/+5V{slash}3V3_16U2") (class "Default")
      (node (ref "C2") (pin "2") (pinfunction "2_2") (pintype "passive"))
      (node (ref "C3") (pin "2") (pinfunction "2_2") (pintype "passive"))
      (node (ref "C4") (pin "2") (pinfunction "2_2") (pintype "passive"))
      (node (ref "FB1") (pin "2") (pinfunction "2_2") (pintype "passive"))
      (node (ref "U1") (pin "32") (pinfunction "AVCC_32") (pintype "power_in"))
      (node (ref "U1") (pin "4") (pinfunction "VCC_4") (pintype "power_in"))
    )
    (net (code "9") (name "/+5V{slash}3V3_328P_AVCC") (class "Default")
      (node (ref "C18") (pin "2") (pinfunction "2_2") (pintype "passive"))
      (node (ref "C19") (pin "2") (pinfunction "2_2") (pintype "passive"))
      (node (ref "FB3") (pin "2") (pinfunction "2_2") (pintype "passive"))
      (node (ref "U2") (pin "20") (pinfunction "AVCC_20") (pintype "power_in"))
    )
    (net (code "10") (name "/+5V{slash}3V3_328P_VCC") (class "Default")
      (node (ref "C12") (pin "2") (pinfunction "2_2") (pintype "passive"))
      (node (ref "C13") (pin "2") (pinfunction "2_2") (pintype "passive"))
      (node (ref "FB2") (pin "2") (pinfunction "2_2") (pintype "passive"))
      (node (ref "U2") (pin "7") (pinfunction "VCC_7") (pintype "power_in"))
    )
    (net (code "11") (name "/16U2PROG_328P_RESETn") (class "Default")
      (node (ref "J2") (pin "2") (pinfunction "2_2") (pintype "passive"))
      (node (ref "R1") (pin "1") (pinfunction "1_1") (pintype "passive"))
      (node (ref "U1") (pin "13") (pinfunction "PD7_(~{CTS}/~{HWB}/AIN6/T0/INT7)_13") (pintype "bidirectional"))
    )
    (net (code "12") (name "/16U2_BUF_RESETn") (class "Default")
      (node (ref "C33") (pin "2") (pinfunction "2_2") (pintype "passive"))
      (node (ref "R23") (pin "2") (pinfunction "2_2") (pintype "passive"))
      (node (ref "U7") (pin "1") (pinfunction "A_1") (pintype "input"))
      (node (ref "U7") (pin "2") (pinfunction "B_2") (pintype "input"))
    )
    (net (code "13") (name "/16U2_HDR_RESETn") (class "Default")
      (node (ref "J3") (pin "5") (pinfunction "5_5") (pintype "passive"))
      (node (ref "J4") (pin "3") (pinfunction "3_3") (pintype "passive"))
    )
    (net (code "14") (name "/16U2_MISO") (class "Default")
      (node (ref "J3") (pin "1") (pinfunction "1_1") (pintype "passive"))
      (node (ref "U1") (pin "17") (pinfunction "PB3_(PDO/MISO/PCINT3)_17") (pintype "bidirectional"))
    )
    (net (code "15") (name "/16U2_MOSI") (class "Default")
      (node (ref "J3") (pin "4") (pinfunction "4_4") (pintype "passive"))
      (node (ref "U1") (pin "16") (pinfunction "PB2_(PDI/MOSI/PCINT2)_16") (pintype "bidirectional"))
    )
    (net (code "16") (name "/16U2_PB4") (class "Default")
      (node (ref "J4") (pin "2") (pinfunction "2_2") (pintype "passive"))
      (node (ref "J5") (pin "1") (pinfunction "1_1") (pintype "passive"))
      (node (ref "U1") (pin "18") (pinfunction "PB4_(T1/PCINT4)_18") (pintype "bidirectional"))
    )
    (net (code "17") (name "/16U2_PB5") (class "Default")
      (node (ref "J5") (pin "3") (pinfunction "3_3") (pintype "passive"))
      (node (ref "U1") (pin "19") (pinfunction "PB5_(PCINT5)_19") (pintype "bidirectional"))
    )
    (net (code "18") (name "/16U2_PB6") (class "Default")
      (node (ref "J5") (pin "2") (pinfunction "2_2") (pintype "passive"))
      (node (ref "U1") (pin "20") (pinfunction "PB6_(PCINT6)_20") (pintype "bidirectional"))
    )
    (net (code "19") (name "/16U2_PB7") (class "Default")
      (node (ref "J5") (pin "4") (pinfunction "4_4") (pintype "passive"))
      (node (ref "U1") (pin "21") (pinfunction "PB7_(PCINT7/OC.0A/OC.1C)_21") (pintype "bidirectional"))
    )
    (net (code "20") (name "/16U2_RESETn") (class "Default")
      (node (ref "J4") (pin "4") (pinfunction "4_4") (pintype "passive"))
      (node (ref "R24") (pin "1") (pinfunction "1_1") (pintype "passive"))
      (node (ref "U1") (pin "24") (pinfunction "~{Reset}_(PC1/dW)_24") (pintype "bidirectional"))
      (node (ref "U7") (pin "4") (pinfunction "Y_4") (pintype "output"))
    )
    (net (code "21") (name "/16U2_RXD") (class "Default")
      (node (ref "R10") (pin "2") (pinfunction "2_2") (pintype "passive"))
      (node (ref "U1") (pin "8") (pinfunction "PD2_(RXD1/AIN1/INT2)_8") (pintype "bidirectional"))
    )
    (net (code "22") (name "/16U2_RX_LED") (class "Default")
      (node (ref "LED1") (pin "1") (pinfunction "K_1") (pintype "passive"))
      (node (ref "U1") (pin "10") (pinfunction "PD4_(INT5/AIN3)_10") (pintype "bidirectional"))
    )
    (net (code "23") (name "/16U2_SCLK") (class "Default")
      (node (ref "J3") (pin "3") (pinfunction "3_3") (pintype "passive"))
      (node (ref "R8") (pin "2") (pinfunction "2_2") (pintype "passive"))
    )
    (net (code "24") (name "/16U2_SCLK_R") (class "Default")
      (node (ref "R8") (pin "1") (pinfunction "1_1") (pintype "passive"))
      (node (ref "U1") (pin "15") (pinfunction "PB1_(SCLK/PCINT1)_15") (pintype "bidirectional"))
    )
    (net (code "25") (name "/16U2_TXD") (class "Default")
      (node (ref "R9") (pin "2") (pinfunction "2_2") (pintype "passive"))
      (node (ref "U1") (pin "9") (pinfunction "PD3_(TXD1/INT3)_9") (pintype "bidirectional"))
    )
    (net (code "26") (name "/16U2_TX_LED") (class "Default")
      (node (ref "LED2") (pin "1") (pinfunction "K_1") (pintype "passive"))
      (node (ref "U1") (pin "11") (pinfunction "PD5_(XCK_AIN4/PCINT12)_11") (pintype "bidirectional"))
    )
    (net (code "27") (name "/328P_16MHZ_XTAL1") (class "Default")
      (node (ref "C27") (pin "1") (pinfunction "1_1") (pintype "passive"))
      (node (ref "R13") (pin "1") (pinfunction "1_1") (pintype "passive"))
      (node (ref "U2") (pin "9") (pinfunction "PB6_(PCINT6/XTAL1/TOSC1)_9") (pintype "bidirectional"))
      (node (ref "Y2") (pin "1") (pinfunction "1_1") (pintype "passive"))
    )
    (net (code "28") (name "/328P_16MHZ_XTAL2") (class "Default")
      (node (ref "C26") (pin "1") (pinfunction "1_1") (pintype "passive"))
      (node (ref "R13") (pin "2") (pinfunction "2_2") (pintype "passive"))
      (node (ref "U2") (pin "10") (pinfunction "PB7_(PCINT7/XTAL2/TOSC2)_10") (pintype "bidirectional"))
      (node (ref "Y2") (pin "2") (pinfunction "2_2") (pintype "passive"))
    )
    (net (code "29") (name "/328P_AUTORESETn") (class "Default")
      (node (ref "C10") (pin "2") (pinfunction "2_2") (pintype "passive"))
      (node (ref "R16") (pin "1") (pinfunction "1_1") (pintype "passive"))
      (node (ref "U5") (pin "1") (pinfunction "A_1") (pintype "input"))
    )
    (net (code "30") (name "/328P_BUF_RESETn") (class "Default")
      (node (ref "C31") (pin "2") (pinfunction "2_2") (pintype "passive"))
      (node (ref "R21") (pin "2") (pinfunction "2_2") (pintype "passive"))
      (node (ref "U5") (pin "2") (pinfunction "B_2") (pintype "input"))
    )
    (net (code "31") (name "/328P_RESETn") (class "Default")
      (node (ref "J12") (pin "5") (pinfunction "5_5") (pintype "passive"))
      (node (ref "J4") (pin "1") (pinfunction "1_1") (pintype "passive"))
      (node (ref "J6") (pin "3") (pinfunction "3_3") (pintype "passive"))
      (node (ref "R11") (pin "1") (pinfunction "1_1") (pintype "passive"))
      (node (ref "U2") (pin "1") (pinfunction "PC6_(PCINT14/~{RESET})_1") (pintype "bidirectional"))
      (node (ref "U5") (pin "4") (pinfunction "Y_4") (pintype "output"))
    )
    (net (code "32") (name "/AD0") (class "Default")
      (node (ref "J7") (pin "1") (pinfunction "1_1") (pintype "passive"))
      (node (ref "U2") (pin "23") (pinfunction "PC0_(ADC0/PCINT8)_23") (pintype "bidirectional"))
    )
    (net (code "33") (name "/AD1") (class "Default")
      (node (ref "J7") (pin "2") (pinfunction "2_2") (pintype "passive"))
      (node (ref "U2") (pin "24") (pinfunction "PC1_(ADC1/PCINT9)_24") (pintype "bidirectional"))
    )
    (net (code "34") (name "/AD2") (class "Default")
      (node (ref "J7") (pin "3") (pinfunction "3_3") (pintype "passive"))
      (node (ref "U2") (pin "25") (pinfunction "PC2_(ADC2/PCINT10)_25") (pintype "bidirectional"))
    )
    (net (code "35") (name "/AD3") (class "Default")
      (node (ref "J7") (pin "4") (pinfunction "4_4") (pintype "passive"))
      (node (ref "U2") (pin "26") (pinfunction "PC3_(ADC3/PCINT11)_26") (pintype "bidirectional"))
    )
    (net (code "36") (name "/AD4{slash}SDA") (class "Default")
      (node (ref "J10") (pin "9") (pinfunction "9_9") (pintype "passive"))
      (node (ref "J7") (pin "5") (pinfunction "5_5") (pintype "passive"))
      (node (ref "U2") (pin "27") (pinfunction "PC4_(ADC4/SDA/PCINT12)_27") (pintype "bidirectional"))
    )
    (net (code "37") (name "/AD5{slash}SCL") (class "Default")
      (node (ref "J10") (pin "10") (pinfunction "10_10") (pintype "passive"))
      (node (ref "J7") (pin "6") (pinfunction "6_6") (pintype "passive"))
      (node (ref "U2") (pin "28") (pinfunction "PC5_(ADC5/SCL/PCINT13)_28") (pintype "bidirectional"))
    )
    (net (code "38") (name "/CON_USB_N") (class "Default")
      (node (ref "J1") (pin "2") (pinfunction "2_2") (pintype "passive"))
      (node (ref "R5") (pin "1") (pinfunction "1_1") (pintype "passive"))
      (node (ref "RV1") (pin "1") (pinfunction "1_1") (pintype "passive"))
    )
    (net (code "39") (name "/CON_USB_P") (class "Default")
      (node (ref "J1") (pin "3") (pinfunction "3_3") (pintype "passive"))
      (node (ref "R7") (pin "1") (pinfunction "1_1") (pintype "passive"))
      (node (ref "RV2") (pin "1") (pinfunction "1_1") (pintype "passive"))
    )
    (net (code "40") (name "/IO0") (class "Default")
      (node (ref "J8") (pin "1") (pinfunction "1_1") (pintype "passive"))
      (node (ref "R9") (pin "1") (pinfunction "1_1") (pintype "passive"))
      (node (ref "U2") (pin "2") (pinfunction "PD0_(PCINT16/RXD)_2") (pintype "bidirectional"))
    )
    (net (code "41") (name "/IO1") (class "Default")
      (node (ref "J8") (pin "2") (pinfunction "2_2") (pintype "passive"))
      (node (ref "R10") (pin "1") (pinfunction "1_1") (pintype "passive"))
      (node (ref "U2") (pin "3") (pinfunction "PD1_(PCINT17/TXD)_3") (pintype "bidirectional"))
    )
    (net (code "42") (name "/IO2") (class "Default")
      (node (ref "J8") (pin "3") (pinfunction "3_3") (pintype "passive"))
      (node (ref "U2") (pin "4") (pinfunction "PD2_(PCINT18/INT0)_4") (pintype "bidirectional"))
    )
    (net (code "43") (name "/IO3") (class "Default")
      (node (ref "J8") (pin "4") (pinfunction "4_4") (pintype "passive"))
      (node (ref "U2") (pin "5") (pinfunction "PD3_(PCINT19/OC2B/INT1)_5") (pintype "bidirectional"))
    )
    (net (code "44") (name "/IO4") (class "Default")
      (node (ref "J8") (pin "5") (pinfunction "5_5") (pintype "passive"))
      (node (ref "U2") (pin "6") (pinfunction "PD4_(PCINT20/XCK/T0)_6") (pintype "bidirectional"))
    )
    (net (code "45") (name "/IO5") (class "Default")
      (node (ref "J8") (pin "6") (pinfunction "6_6") (pintype "passive"))
      (node (ref "U2") (pin "11") (pinfunction "PD5_(PCINT21/OC0B/T1)_11") (pintype "bidirectional"))
    )
    (net (code "46") (name "/IO6") (class "Default")
      (node (ref "J8") (pin "7") (pinfunction "7_7") (pintype "passive"))
      (node (ref "U2") (pin "12") (pinfunction "PD6_(PCINT22/OC0A/AIN0)_12") (pintype "bidirectional"))
    )
    (net (code "47") (name "/IO7") (class "Default")
      (node (ref "J8") (pin "8") (pinfunction "8_8") (pintype "passive"))
      (node (ref "U2") (pin "13") (pinfunction "PD7_(PCINT23/AIN1)_13") (pintype "bidirectional"))
    )
    (net (code "48") (name "/IO8") (class "Default")
      (node (ref "J10") (pin "1") (pinfunction "1_1") (pintype "passive"))
      (node (ref "R20") (pin "1") (pinfunction "1_1") (pintype "passive"))
      (node (ref "U2") (pin "14") (pinfunction "PB0_(PCINT0/CLKO/ICP1)_14") (pintype "bidirectional"))
    )
    (net (code "49") (name "/IO9") (class "Default")
      (node (ref "J10") (pin "2") (pinfunction "2_2") (pintype "passive"))
      (node (ref "U2") (pin "15") (pinfunction "PB1_(OC1A/PCINT1)_15") (pintype "bidirectional"))
    )
    (net (code "50") (name "/MISO") (class "Default")
      (node (ref "J10") (pin "5") (pinfunction "5_5") (pintype "passive"))
      (node (ref "J12") (pin "1") (pinfunction "1_1") (pintype "passive"))
      (node (ref "U2") (pin "18") (pinfunction "PB4_(MISO/PCINT4)_18") (pintype "bidirectional"))
    )
    (net (code "51") (name "/MOSI") (class "Default")
      (node (ref "J10") (pin "4") (pinfunction "4_4") (pintype "passive"))
      (node (ref "J12") (pin "4") (pinfunction "4_4") (pintype "passive"))
      (node (ref "U2") (pin "17") (pinfunction "PB3_(MOSI/OC2A/PCINT3)_17") (pintype "bidirectional"))
    )
    (net (code "52") (name "/SCK") (class "Default")
      (node (ref "J10") (pin "6") (pinfunction "6_6") (pintype "passive"))
      (node (ref "J12") (pin "3") (pinfunction "3_3") (pintype "passive"))
      (node (ref "R12") (pin "2") (pinfunction "2_2") (pintype "passive"))
      (node (ref "U4") (pin "1") (pinfunction "A_1") (pintype "input"))
      (node (ref "U4") (pin "2") (pinfunction "B_2") (pintype "input"))
    )
    (net (code "53") (name "/SCK_R") (class "Default")
      (node (ref "R12") (pin "1") (pinfunction "1_1") (pintype "passive"))
      (node (ref "U2") (pin "19") (pinfunction "PB5_(SCK/PCINT5)_19") (pintype "bidirectional"))
    )
    (net (code "54") (name "/SS") (class "Default")
      (node (ref "J10") (pin "3") (pinfunction "3_3") (pintype "passive"))
      (node (ref "U2") (pin "16") (pinfunction "PB2_(~{SS}/OC1B/PCINT2)_16") (pintype "bidirectional"))
    )
    (net (code "55") (name "/USB_N") (class "Default")
      (node (ref "R5") (pin "2") (pinfunction "2_2") (pintype "passive"))
      (node (ref "U1") (pin "30") (pinfunction "D-_30") (pintype "bidirectional"))
    )
    (net (code "56") (name "/USB_P") (class "Default")
      (node (ref "R7") (pin "2") (pinfunction "2_2") (pintype "passive"))
      (node (ref "U1") (pin "29") (pinfunction "D+_29") (pintype "bidirectional"))
    )
    (net (code "57") (name "/USER_BUTTON_BUF") (class "Default")
      (node (ref "C32") (pin "2") (pinfunction "2_2") (pintype "passive"))
      (node (ref "R22") (pin "2") (pinfunction "2_2") (pintype "passive"))
      (node (ref "U6") (pin "1") (pinfunction "A_1") (pintype "input"))
      (node (ref "U6") (pin "2") (pinfunction "B_2") (pintype "input"))
    )
    (net (code "58") (name "GND") (class "Default")
      (node (ref "C1") (pin "2") (pinfunction "2_2") (pintype "passive"))
      (node (ref "C11") (pin "1") (pinfunction "1_1") (pintype "passive"))
      (node (ref "C12") (pin "1") (pinfunction "1_1") (pintype "passive"))
      (node (ref "C13") (pin "1") (pinfunction "1_1") (pintype "passive"))
      (node (ref "C14") (pin "1") (pinfunction "1_1") (pintype "passive"))
      (node (ref "C15") (pin "1") (pinfunction "1_1") (pintype "passive"))
      (node (ref "C16") (pin "1") (pinfunction "1_1") (pintype "passive"))
      (node (ref "C17") (pin "1") (pinfunction "1_1") (pintype "passive"))
      (node (ref "C18") (pin "1") (pinfunction "1_1") (pintype "passive"))
      (node (ref "C19") (pin "1") (pinfunction "1_1") (pintype "passive"))
      (node (ref "C2") (pin "1") (pinfunction "1_1") (pintype "passive"))
      (node (ref "C20") (pin "1") (pinfunction "1_1") (pintype "passive"))
      (node (ref "C21") (pin "1") (pinfunction "1_1") (pintype "passive"))
      (node (ref "C22") (pin "1") (pinfunction "1_1") (pintype "passive"))
      (node (ref "C23") (pin "1") (pinfunction "1_1") (pintype "passive"))
      (node (ref "C24") (pin "1") (pinfunction "1_1") (pintype "passive"))
      (node (ref "C25") (pin "1") (pinfunction "1_1") (pintype "passive"))
      (node (ref "C26") (pin "2") (pinfunction "2_2") (pintype "passive"))
      (node (ref "C27") (pin "2") (pinfunction "2_2") (pintype "passive"))
      (node (ref "C28") (pin "1") (pinfunction "1_1") (pintype "passive"))
      (node (ref "C29") (pin "1") (pinfunction "1_1") (pintype "passive"))
      (node (ref "C3") (pin "1") (pinfunction "1_1") (pintype "passive"))
      (node (ref "C30") (pin "1") (pinfunction "1_1") (pintype "passive"))
      (node (ref "C31") (pin "1") (pinfunction "1_1") (pintype "passive"))
      (node (ref "C32") (pin "1") (pinfunction "1_1") (pintype "passive"))
      (node (ref "C33") (pin "1") (pinfunction "1_1") (pintype "passive"))
      (node (ref "C4") (pin "1") (pinfunction "1_1") (pintype "passive"))
      (node (ref "C5") (pin "2") (pinfunction "2_2") (pintype "passive"))
      (node (ref "C6") (pin "1") (pinfunction "C_1") (pintype "passive"))
      (node (ref "C7") (pin "1") (pinfunction "C_1") (pintype "passive"))
      (node (ref "C8") (pin "1") (pinfunction "1_1") (pintype "passive"))
      (node (ref "C9") (pin "2") (pinfunction "2_2") (pintype "passive"))
      (node (ref "D1") (pin "1") (pinfunction "C_1") (pintype "passive"))
      (node (ref "J1") (pin "4") (pinfunction "4_4") (pintype "passive"))
      (node (ref "J1") (pin "5") (pinfunction "5_5") (pintype "passive"))
      (node (ref "J1") (pin "MH1") (pinfunction "MH1_MH1") (pintype "passive"))
      (node (ref "J1") (pin "MH2") (pinfunction "MH2_MH2") (pintype "passive"))
      (node (ref "J1") (pin "MP1") (pinfunction "MP1_MP1") (pintype "passive"))
      (node (ref "J1") (pin "MP2") (pinfunction "MP2_MP2") (pintype "passive"))
      (node (ref "J1") (pin "MP3") (pinfunction "MP3_MP3") (pintype "passive"))
      (node (ref "J1") (pin "MP4") (pinfunction "MP4_MP4") (pintype "passive"))
      (node (ref "J10") (pin "7") (pinfunction "7_7") (pintype "passive"))
      (node (ref "J11") (pin "1") (pinfunction "1_1") (pintype "passive"))
      (node (ref "J3") (pin "6") (pinfunction "6_6") (pintype "passive"))
      (node (ref "J6") (pin "6") (pinfunction "6_6") (pintype "passive"))
      (node (ref "J6") (pin "7") (pinfunction "7_7") (pintype "passive"))
      (node (ref "MH1") (pin "1") (pinfunction "1_1") (pintype "passive"))
      (node (ref "MH2") (pin "1") (pinfunction "1_1") (pintype "passive"))
      (node (ref "MH3") (pin "1") (pinfunction "1_1") (pintype "passive"))
      (node (ref "R6") (pin "2") (pinfunction "2_2") (pintype "passive"))
      (node (ref "RV1") (pin "2") (pinfunction "2_2") (pintype "passive"))
      (node (ref "RV2") (pin "2") (pinfunction "2_2") (pintype "passive"))
      (node (ref "SW1") (pin "3") (pinfunction "3_3") (pintype "passive"))
      (node (ref "SW1") (pin "4") (pinfunction "4_4") (pintype "passive"))
      (node (ref "SW2") (pin "3") (pinfunction "3_3") (pintype "passive"))
      (node (ref "SW2") (pin "4") (pinfunction "4_4") (pintype "passive"))
      (node (ref "U1") (pin "28") (pinfunction "UGND_28") (pintype "power_in"))
      (node (ref "U1") (pin "3") (pinfunction "GND_3") (pintype "power_in"))
      (node (ref "U2") (pin "22") (pinfunction "GND_22") (pintype "power_in"))
      (node (ref "U2") (pin "8") (pinfunction "GND_8") (pintype "power_in"))
      (node (ref "U3") (pin "3") (pinfunction "GND_3") (pintype "power_in"))
      (node (ref "U3") (pin "6") (pinfunction "GND_6") (pintype "power_in"))
      (node (ref "U4") (pin "3") (pinfunction "GND_3") (pintype "power_in"))
      (node (ref "U5") (pin "3") (pinfunction "GND_3") (pintype "power_in"))
      (node (ref "U6") (pin "3") (pinfunction "GND_3") (pintype "power_in"))
      (node (ref "U7") (pin "3") (pinfunction "GND_3") (pintype "power_in"))
    )
    (net (code "59") (name "Net-(C10-Pad1)") (class "Default")
      (node (ref "C10") (pin "1") (pinfunction "1_1") (pintype "passive"))
      (node (ref "J2") (pin "1") (pinfunction "1_1") (pintype "passive"))
    )
    (net (code "60") (name "Net-(D1-A)") (class "Default")
      (node (ref "D1") (pin "2") (pinfunction "A_2") (pintype "passive"))
      (node (ref "R15") (pin "1") (pinfunction "1_1") (pintype "passive"))
    )
    (net (code "61") (name "Net-(D2-A)") (class "Default")
      (node (ref "D2") (pin "2") (pinfunction "A_2") (pintype "passive"))
      (node (ref "R17") (pin "1") (pinfunction "1_1") (pintype "passive"))
      (node (ref "R21") (pin "1") (pinfunction "1_1") (pintype "passive"))
      (node (ref "SW1") (pin "1") (pinfunction "1_1") (pintype "passive"))
      (node (ref "SW1") (pin "2") (pinfunction "2_2") (pintype "passive"))
    )
    (net (code "62") (name "Net-(D3-A)") (class "Default")
      (node (ref "D3") (pin "2") (pinfunction "A_2") (pintype "passive"))
      (node (ref "R19") (pin "1") (pinfunction "1_1") (pintype "passive"))
      (node (ref "R23") (pin "1") (pinfunction "1_1") (pintype "passive"))
    )
    (net (code "63") (name "Net-(J2-Pad3)") (class "Default")
      (node (ref "J2") (pin "3") (pinfunction "3_3") (pintype "passive"))
      (node (ref "R6") (pin "1") (pinfunction "1_1") (pintype "passive"))
    )
    (net (code "64") (name "Net-(LED1-A)") (class "Default")
      (node (ref "LED1") (pin "2") (pinfunction "A_2") (pintype "passive"))
      (node (ref "R3") (pin "1") (pinfunction "1_1") (pintype "passive"))
    )
    (net (code "65") (name "Net-(LED2-A)") (class "Default")
      (node (ref "LED2") (pin "2") (pinfunction "A_2") (pintype "passive"))
      (node (ref "R4") (pin "1") (pinfunction "1_1") (pintype "passive"))
    )
    (net (code "66") (name "Net-(LED3-A)") (class "Default")
      (node (ref "LED3") (pin "2") (pinfunction "A_2") (pintype "passive"))
      (node (ref "R14") (pin "1") (pinfunction "1_1") (pintype "passive"))
    )
    (net (code "67") (name "Net-(LED3-K)") (class "Default")
      (node (ref "LED3") (pin "1") (pinfunction "K_1") (pintype "passive"))
      (node (ref "U4") (pin "4") (pinfunction "Y_4") (pintype "output"))
    )
    (net (code "68") (name "Net-(R18-Pad1)") (class "Default")
      (node (ref "R18") (pin "1") (pinfunction "1_1") (pintype "passive"))
      (node (ref "R22") (pin "1") (pinfunction "1_1") (pintype "passive"))
      (node (ref "SW2") (pin "1") (pinfunction "1_1") (pintype "passive"))
      (node (ref "SW2") (pin "2") (pinfunction "2_2") (pintype "passive"))
    )
    (net (code "69") (name "Net-(U1-(PC0)_XTAL2)") (class "Default")
      (node (ref "C5") (pin "1") (pinfunction "1_1") (pintype "passive"))
      (node (ref "R2") (pin "2") (pinfunction "2_2") (pintype "passive"))
      (node (ref "U1") (pin "2") (pinfunction "(PC0)_XTAL2_2") (pintype "bidirectional"))
      (node (ref "Y1") (pin "2") (pinfunction "2_2") (pintype "passive"))
    )
    (net (code "70") (name "Net-(U1-XTAL1)") (class "Default")
      (node (ref "C1") (pin "1") (pinfunction "1_1") (pintype "passive"))
      (node (ref "R2") (pin "1") (pinfunction "1_1") (pintype "passive"))
      (node (ref "U1") (pin "1") (pinfunction "XTAL1_1") (pintype "input"))
      (node (ref "Y1") (pin "1") (pinfunction "1_1") (pintype "passive"))
    )
    (net (code "71") (name "Net-(U6-Y)") (class "Default")
      (node (ref "R20") (pin "2") (pinfunction "2_2") (pintype "passive"))
      (node (ref "U6") (pin "4") (pinfunction "Y_4") (pintype "output"))
    )
    (net (code "72") (name "unconnected-(J2-Pad4)") (class "Default")
      (node (ref "J2") (pin "4") (pinfunction "4_4") (pintype "passive+no_connect"))
    )
    (net (code "73") (name "unconnected-(J6-Pad1)") (class "Default")
      (node (ref "J6") (pin "1") (pinfunction "1_1") (pintype "passive+no_connect"))
    )
    (net (code "74") (name "unconnected-(J6-Pad8)") (class "Default")
      (node (ref "J6") (pin "8") (pinfunction "8_8") (pintype "passive+no_connect"))
    )
    (net (code "75") (name "unconnected-(J12-Pad6)") (class "Default")
      (node (ref "J12") (pin "6") (pinfunction "6_6") (pintype "passive"))
    )
    (net (code "76") (name "unconnected-(MH4-Pad1)") (class "Default")
      (node (ref "MH4") (pin "1") (pinfunction "1_1") (pintype "passive+no_connect"))
    )
    (net (code "77") (name "unconnected-(U1-PB0_(~{SS}{slash}PCINT0)-Pad14)") (class "Default")
      (node (ref "U1") (pin "14") (pinfunction "PB0_(~{SS}/PCINT0)_14") (pintype "bidirectional+no_connect"))
    )
    (net (code "78") (name "unconnected-(U1-PC2_(PCINT11{slash}AIN2)-Pad5)") (class "Default")
      (node (ref "U1") (pin "5") (pinfunction "PC2_(PCINT11/AIN2)_5") (pintype "bidirectional+no_connect"))
    )
    (net (code "79") (name "unconnected-(U1-PC4_(PCINT10)-Pad26)") (class "Default")
      (node (ref "U1") (pin "26") (pinfunction "PC4_(PCINT10)_26") (pintype "bidirectional+no_connect"))
    )
    (net (code "80") (name "unconnected-(U1-PC5_(PCINT9{slash}OC.1B)-Pad25)") (class "Default")
      (node (ref "U1") (pin "25") (pinfunction "PC5_(PCINT9/OC.1B)_25") (pintype "bidirectional+no_connect"))
    )
    (net (code "81") (name "unconnected-(U1-PC6_(OC.1A{slash}PCINT8)-Pad23)") (class "Default")
      (node (ref "U1") (pin "23") (pinfunction "PC6_(OC.1A/PCINT8)_23") (pintype "bidirectional+no_connect"))
    )
    (net (code "82") (name "unconnected-(U1-PC7_(INT4{slash}ICP1{slash}CLKO)-Pad22)") (class "Default")
      (node (ref "U1") (pin "22") (pinfunction "PC7_(INT4/ICP1/CLKO)_22") (pintype "bidirectional+no_connect"))
    )
    (net (code "83") (name "unconnected-(U1-PD0_(OC.0B{slash}INT0)-Pad6)") (class "Default")
      (node (ref "U1") (pin "6") (pinfunction "PD0_(OC.0B/INT0)_6") (pintype "bidirectional+no_connect"))
    )
    (net (code "84") (name "unconnected-(U1-PD1_(AIN0{slash}INT1)-Pad7)") (class "Default")
      (node (ref "U1") (pin "7") (pinfunction "PD1_(AIN0/INT1)_7") (pintype "bidirectional+no_connect"))
    )
    (net (code "85") (name "unconnected-(U1-PD6_(~{RTS}{slash}AIN5{slash}INT6)-Pad12)") (class "Default")
      (node (ref "U1") (pin "12") (pinfunction "PD6_(~{RTS}/AIN5/INT6)_12") (pintype "bidirectional+no_connect"))
    )
  )
)
